# HC-05or06-Breakout.net
KiCad netlist of a schematic drawn in EAGLE
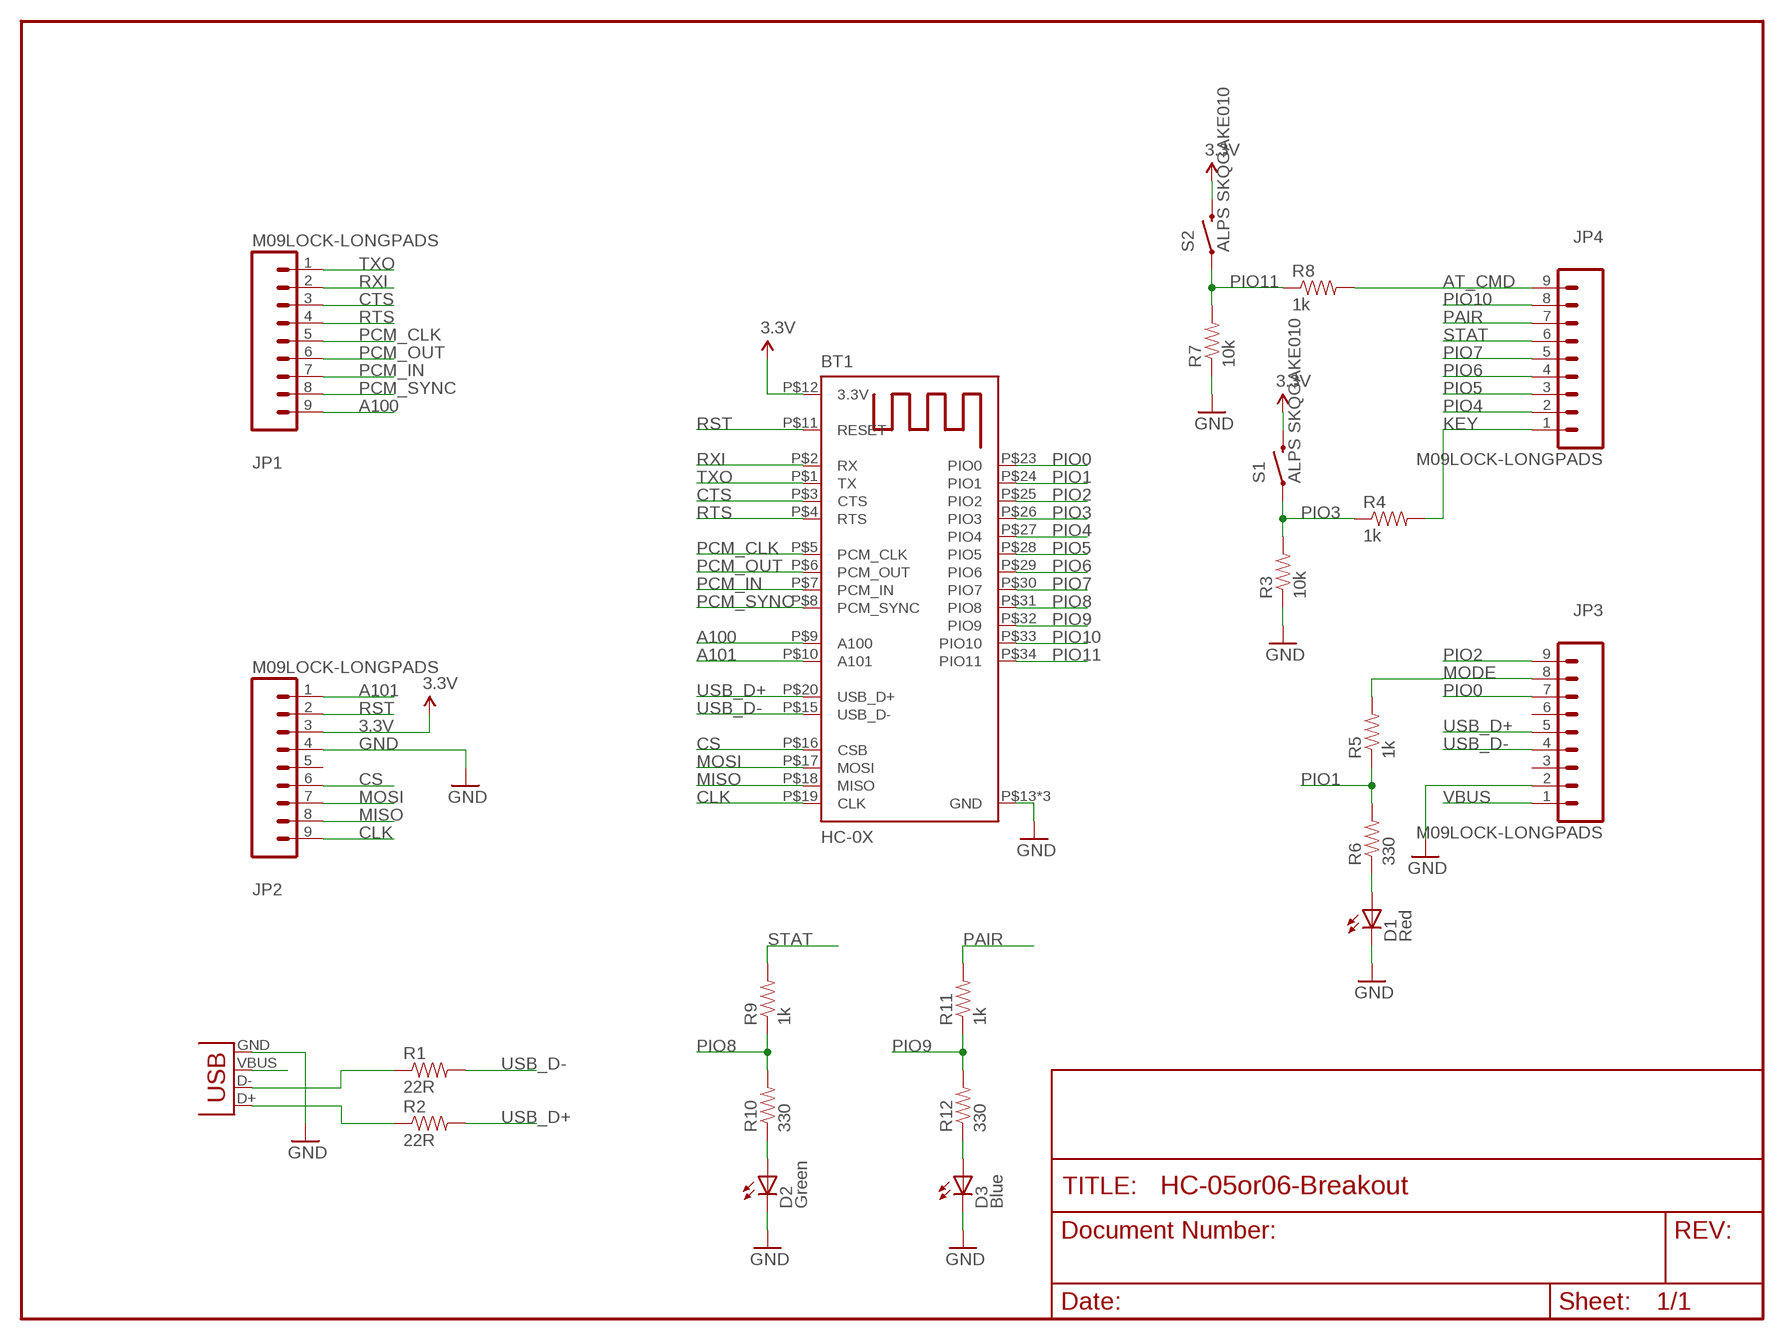
[diagram p0: schematic, sheet 1]

(export (version "E")
  (design (tool "Eeschema 10.0.6"))
  (components
    (comp (ref "BT1")
      (value "HC-0X")
      (footprint "eagle-import:HC-0X")
      (libsource (lib "eagle-import") (part "HC-0X"))
    )
    (comp (ref "D1")
      (value "Red")
      (footprint "eagle-import:LED-0603")
      (libsource (lib "eagle-import") (part "LED0603"))
    )
    (comp (ref "D2")
      (value "Green")
      (footprint "eagle-import:LED-0603")
      (libsource (lib "eagle-import") (part "LED0603"))
    )
    (comp (ref "D3")
      (value "Blue")
      (footprint "eagle-import:LED-0603")
      (libsource (lib "eagle-import") (part "LED0603"))
    )
    (comp (ref "JP1")
      (value "M09LOCK-LONGPADS")
      (footprint "eagle-import:1X09_LOCK_LONGPADS")
      (libsource (lib "eagle-import") (part "M09LOCK-LONGPADS"))
    )
    (comp (ref "JP2")
      (value "M09LOCK-LONGPADS")
      (footprint "eagle-import:1X09_LOCK_LONGPADS")
      (libsource (lib "eagle-import") (part "M09LOCK-LONGPADS"))
    )
    (comp (ref "JP3")
      (value "M09LOCK-LONGPADS")
      (footprint "eagle-import:1X09_LOCK_LONGPADS")
      (libsource (lib "eagle-import") (part "M09LOCK-LONGPADS"))
    )
    (comp (ref "JP4")
      (value "M09LOCK-LONGPADS")
      (footprint "eagle-import:1X09_LOCK_LONGPADS")
      (libsource (lib "eagle-import") (part "M09LOCK-LONGPADS"))
    )
    (comp (ref "R1")
      (value "22R")
      (footprint "eagle-import:0603-RES")
      (libsource (lib "eagle-import") (part "RESISTOR0603-RES"))
    )
    (comp (ref "R2")
      (value "22R")
      (footprint "eagle-import:0603-RES")
      (libsource (lib "eagle-import") (part "RESISTOR0603-RES"))
    )
    (comp (ref "R3")
      (value "10k")
      (footprint "eagle-import:0603-RES")
      (libsource (lib "eagle-import") (part "RESISTOR0603-RES"))
    )
    (comp (ref "R4")
      (value "1k")
      (footprint "eagle-import:0603-RES")
      (libsource (lib "eagle-import") (part "RESISTOR0603-RES"))
    )
    (comp (ref "R5")
      (value "1k")
      (footprint "eagle-import:0603-RES")
      (libsource (lib "eagle-import") (part "RESISTOR0603-RES"))
    )
    (comp (ref "R6")
      (value "330")
      (footprint "eagle-import:0603-RES")
      (libsource (lib "eagle-import") (part "RESISTOR0603-RES"))
    )
    (comp (ref "R7")
      (value "10k")
      (footprint "eagle-import:0603-RES")
      (libsource (lib "eagle-import") (part "RESISTOR0603-RES"))
    )
    (comp (ref "R8")
      (value "1k")
      (footprint "eagle-import:0603-RES")
      (libsource (lib "eagle-import") (part "RESISTOR0603-RES"))
    )
    (comp (ref "R9")
      (value "1k")
      (footprint "eagle-import:0603-RES")
      (libsource (lib "eagle-import") (part "RESISTOR0603-RES"))
    )
    (comp (ref "R10")
      (value "330")
      (footprint "eagle-import:0603-RES")
      (libsource (lib "eagle-import") (part "RESISTOR0603-RES"))
    )
    (comp (ref "R11")
      (value "1k")
      (footprint "eagle-import:0603-RES")
      (libsource (lib "eagle-import") (part "RESISTOR0603-RES"))
    )
    (comp (ref "R12")
      (value "330")
      (footprint "eagle-import:0603-RES")
      (libsource (lib "eagle-import") (part "RESISTOR0603-RES"))
    )
    (comp (ref "S1")
      (value "ALPS SKQGAKE010")
      (footprint "eagle-import:TACTILE_SWITCH_SMD")
      (libsource (lib "eagle-import") (part "SWITCH-MOMENTARY-2SMD"))
    )
    (comp (ref "S2")
      (value "ALPS SKQGAKE010")
      (footprint "eagle-import:TACTILE_SWITCH_SMD")
      (libsource (lib "eagle-import") (part "SWITCH-MOMENTARY-2SMD"))
    )
    (comp (ref "X1")
      (value "USBSMD")
      (footprint "eagle-import:USB-MINIB")
      (libsource (lib "eagle-import") (part "USBSMD"))
    )
  )
  (nets
    (net (code "1") (name "/A100") (class "Default")
      (node (ref "BT1") (pin "P$9") (pinfunction "A100_P$9") (pintype "bidirectional"))
      (node (ref "JP1") (pin "9") (pinfunction "9_9") (pintype "passive"))
    )
    (net (code "2") (name "/A101") (class "Default")
      (node (ref "BT1") (pin "P$10") (pinfunction "A101_P$10") (pintype "bidirectional"))
      (node (ref "JP2") (pin "1") (pinfunction "1_1") (pintype "passive"))
    )
    (net (code "3") (name "/AT_CMD") (class "Default")
      (node (ref "JP4") (pin "9") (pinfunction "9_9") (pintype "passive"))
      (node (ref "R8") (pin "2") (pinfunction "2_2") (pintype "passive"))
    )
    (net (code "4") (name "/CLK") (class "Default")
      (node (ref "BT1") (pin "P$19") (pinfunction "CLK_P$19") (pintype "bidirectional"))
      (node (ref "JP2") (pin "9") (pinfunction "9_9") (pintype "passive"))
    )
    (net (code "5") (name "/CS") (class "Default")
      (node (ref "BT1") (pin "P$16") (pinfunction "CSB_P$16") (pintype "bidirectional"))
      (node (ref "JP2") (pin "6") (pinfunction "6_6") (pintype "passive"))
    )
    (net (code "6") (name "/CTS") (class "Default")
      (node (ref "BT1") (pin "P$3") (pinfunction "CTS_P$3") (pintype "bidirectional"))
      (node (ref "JP1") (pin "3") (pinfunction "3_3") (pintype "passive"))
    )
    (net (code "7") (name "/KEY") (class "Default")
      (node (ref "JP4") (pin "1") (pinfunction "1_1") (pintype "passive"))
      (node (ref "R4") (pin "2") (pinfunction "2_2") (pintype "passive"))
    )
    (net (code "8") (name "/MISO") (class "Default")
      (node (ref "BT1") (pin "P$18") (pinfunction "MISO_P$18") (pintype "bidirectional"))
      (node (ref "JP2") (pin "8") (pinfunction "8_8") (pintype "passive"))
    )
    (net (code "9") (name "/MODE") (class "Default")
      (node (ref "JP3") (pin "8") (pinfunction "8_8") (pintype "passive"))
      (node (ref "R5") (pin "2") (pinfunction "2_2") (pintype "passive"))
    )
    (net (code "10") (name "/MOSI") (class "Default")
      (node (ref "BT1") (pin "P$17") (pinfunction "MOSI_P$17") (pintype "bidirectional"))
      (node (ref "JP2") (pin "7") (pinfunction "7_7") (pintype "passive"))
    )
    (net (code "11") (name "/PAIR") (class "Default")
      (node (ref "JP4") (pin "7") (pinfunction "7_7") (pintype "passive"))
      (node (ref "R11") (pin "2") (pinfunction "2_2") (pintype "passive"))
    )
    (net (code "12") (name "/PCM_CLK") (class "Default")
      (node (ref "BT1") (pin "P$5") (pinfunction "PCM_CLK_P$5") (pintype "bidirectional"))
      (node (ref "JP1") (pin "5") (pinfunction "5_5") (pintype "passive"))
    )
    (net (code "13") (name "/PCM_IN") (class "Default")
      (node (ref "BT1") (pin "P$7") (pinfunction "PCM_IN_P$7") (pintype "bidirectional"))
      (node (ref "JP1") (pin "7") (pinfunction "7_7") (pintype "passive"))
    )
    (net (code "14") (name "/PCM_OUT") (class "Default")
      (node (ref "BT1") (pin "P$6") (pinfunction "PCM_OUT_P$6") (pintype "bidirectional"))
      (node (ref "JP1") (pin "6") (pinfunction "6_6") (pintype "passive"))
    )
    (net (code "15") (name "/PCM_SYNC") (class "Default")
      (node (ref "BT1") (pin "P$8") (pinfunction "PCM_SYNC_P$8") (pintype "bidirectional"))
      (node (ref "JP1") (pin "8") (pinfunction "8_8") (pintype "passive"))
    )
    (net (code "16") (name "/PIO0") (class "Default")
      (node (ref "BT1") (pin "P$23") (pinfunction "PIO0_P$23") (pintype "bidirectional"))
      (node (ref "JP3") (pin "7") (pinfunction "7_7") (pintype "passive"))
    )
    (net (code "17") (name "/PIO1") (class "Default")
      (node (ref "BT1") (pin "P$24") (pinfunction "PIO1_P$24") (pintype "bidirectional"))
      (node (ref "R5") (pin "1") (pinfunction "1_1") (pintype "passive"))
      (node (ref "R6") (pin "2") (pinfunction "2_2") (pintype "passive"))
    )
    (net (code "18") (name "/PIO2") (class "Default")
      (node (ref "BT1") (pin "P$25") (pinfunction "PIO2_P$25") (pintype "bidirectional"))
      (node (ref "JP3") (pin "9") (pinfunction "9_9") (pintype "passive"))
    )
    (net (code "19") (name "/PIO3") (class "Default")
      (node (ref "BT1") (pin "P$26") (pinfunction "PIO3_P$26") (pintype "bidirectional"))
      (node (ref "R3") (pin "2") (pinfunction "2_2") (pintype "passive"))
      (node (ref "R4") (pin "1") (pinfunction "1_1") (pintype "passive"))
      (node (ref "S1") (pin "1") (pinfunction "1_1") (pintype "passive"))
    )
    (net (code "20") (name "/PIO4") (class "Default")
      (node (ref "BT1") (pin "P$27") (pinfunction "PIO4_P$27") (pintype "bidirectional"))
      (node (ref "JP4") (pin "2") (pinfunction "2_2") (pintype "passive"))
    )
    (net (code "21") (name "/PIO5") (class "Default")
      (node (ref "BT1") (pin "P$28") (pinfunction "PIO5_P$28") (pintype "bidirectional"))
      (node (ref "JP4") (pin "3") (pinfunction "3_3") (pintype "passive"))
    )
    (net (code "22") (name "/PIO6") (class "Default")
      (node (ref "BT1") (pin "P$29") (pinfunction "PIO6_P$29") (pintype "bidirectional"))
      (node (ref "JP4") (pin "4") (pinfunction "4_4") (pintype "passive"))
    )
    (net (code "23") (name "/PIO7") (class "Default")
      (node (ref "BT1") (pin "P$30") (pinfunction "PIO7_P$30") (pintype "bidirectional"))
      (node (ref "JP4") (pin "5") (pinfunction "5_5") (pintype "passive"))
    )
    (net (code "24") (name "/PIO8") (class "Default")
      (node (ref "BT1") (pin "P$31") (pinfunction "PIO8_P$31") (pintype "bidirectional"))
      (node (ref "R10") (pin "2") (pinfunction "2_2") (pintype "passive"))
      (node (ref "R9") (pin "1") (pinfunction "1_1") (pintype "passive"))
    )
    (net (code "25") (name "/PIO9") (class "Default")
      (node (ref "BT1") (pin "P$32") (pinfunction "PIO9_P$32") (pintype "bidirectional"))
      (node (ref "R11") (pin "1") (pinfunction "1_1") (pintype "passive"))
      (node (ref "R12") (pin "2") (pinfunction "2_2") (pintype "passive"))
    )
    (net (code "26") (name "/PIO10") (class "Default")
      (node (ref "BT1") (pin "P$33") (pinfunction "PIO10_P$33") (pintype "bidirectional"))
      (node (ref "JP4") (pin "8") (pinfunction "8_8") (pintype "passive"))
    )
    (net (code "27") (name "/PIO11") (class "Default")
      (node (ref "BT1") (pin "P$34") (pinfunction "PIO11_P$34") (pintype "bidirectional"))
      (node (ref "R7") (pin "2") (pinfunction "2_2") (pintype "passive"))
      (node (ref "R8") (pin "1") (pinfunction "1_1") (pintype "passive"))
      (node (ref "S2") (pin "1") (pinfunction "1_1") (pintype "passive"))
    )
    (net (code "28") (name "/RST") (class "Default")
      (node (ref "BT1") (pin "P$11") (pinfunction "RESET_P$11") (pintype "bidirectional"))
      (node (ref "JP2") (pin "2") (pinfunction "2_2") (pintype "passive"))
    )
    (net (code "29") (name "/RTS") (class "Default")
      (node (ref "BT1") (pin "P$4") (pinfunction "RTS_P$4") (pintype "bidirectional"))
      (node (ref "JP1") (pin "4") (pinfunction "4_4") (pintype "passive"))
    )
    (net (code "30") (name "/RXI") (class "Default")
      (node (ref "BT1") (pin "P$2") (pinfunction "RX_P$2") (pintype "bidirectional"))
      (node (ref "JP1") (pin "2") (pinfunction "2_2") (pintype "passive"))
    )
    (net (code "31") (name "/STAT") (class "Default")
      (node (ref "JP4") (pin "6") (pinfunction "6_6") (pintype "passive"))
      (node (ref "R9") (pin "2") (pinfunction "2_2") (pintype "passive"))
    )
    (net (code "32") (name "/TXO") (class "Default")
      (node (ref "BT1") (pin "P$1") (pinfunction "TX_P$1") (pintype "bidirectional"))
      (node (ref "JP1") (pin "1") (pinfunction "1_1") (pintype "passive"))
    )
    (net (code "33") (name "/USB_D+") (class "Default")
      (node (ref "BT1") (pin "P$20") (pinfunction "USB_D+_P$20") (pintype "bidirectional"))
      (node (ref "JP3") (pin "5") (pinfunction "5_5") (pintype "passive"))
      (node (ref "R2") (pin "2") (pinfunction "2_2") (pintype "passive"))
    )
    (net (code "34") (name "/USB_D-") (class "Default")
      (node (ref "BT1") (pin "P$15") (pinfunction "USB_D-_P$15") (pintype "bidirectional"))
      (node (ref "JP3") (pin "4") (pinfunction "4_4") (pintype "passive"))
      (node (ref "R1") (pin "2") (pinfunction "2_2") (pintype "passive"))
    )
    (net (code "35") (name "/VBUS") (class "Default")
      (node (ref "JP3") (pin "1") (pinfunction "1_1") (pintype "passive"))
      (node (ref "X1") (pin "VBUS") (pinfunction "VBUS_VBUS") (pintype "bidirectional"))
    )
    (net (code "36") (name "3.3V") (class "Default")
      (node (ref "BT1") (pin "P$12") (pinfunction "3.3V_P$12") (pintype "bidirectional"))
      (node (ref "JP2") (pin "3") (pinfunction "3_3") (pintype "passive"))
      (node (ref "S1") (pin "3") (pinfunction "2_3") (pintype "passive"))
      (node (ref "S2") (pin "3") (pinfunction "2_3") (pintype "passive"))
    )
    (net (code "37") (name "GND") (class "Default")
      (node (ref "BT1") (pin "P$13") (pinfunction "GND_P$13") (pintype "bidirectional"))
      (node (ref "BT1") (pin "P$21") (pinfunction "GND_P$21") (pintype "bidirectional"))
      (node (ref "BT1") (pin "P$22") (pinfunction "GND_P$22") (pintype "bidirectional"))
      (node (ref "D1") (pin "C") (pinfunction "C_C") (pintype "passive"))
      (node (ref "D2") (pin "C") (pinfunction "C_C") (pintype "passive"))
      (node (ref "D3") (pin "C") (pinfunction "C_C") (pintype "passive"))
      (node (ref "JP2") (pin "4") (pinfunction "4_4") (pintype "passive"))
      (node (ref "JP3") (pin "2") (pinfunction "2_2") (pintype "passive"))
      (node (ref "R3") (pin "1") (pinfunction "1_1") (pintype "passive"))
      (node (ref "R7") (pin "1") (pinfunction "1_1") (pintype "passive"))
      (node (ref "X1") (pin "GND") (pinfunction "GND_GND") (pintype "bidirectional"))
    )
    (net (code "38") (name "Net-(D1-PadA)") (class "Default")
      (node (ref "D1") (pin "A") (pinfunction "A_A") (pintype "passive"))
      (node (ref "R6") (pin "1") (pinfunction "1_1") (pintype "passive"))
    )
    (net (code "39") (name "Net-(D2-PadA)") (class "Default")
      (node (ref "D2") (pin "A") (pinfunction "A_A") (pintype "passive"))
      (node (ref "R10") (pin "1") (pinfunction "1_1") (pintype "passive"))
    )
    (net (code "40") (name "Net-(D3-PadA)") (class "Default")
      (node (ref "D3") (pin "A") (pinfunction "A_A") (pintype "passive"))
      (node (ref "R12") (pin "1") (pinfunction "1_1") (pintype "passive"))
    )
    (net (code "41") (name "Net-(R1-Pad1)") (class "Default")
      (node (ref "R1") (pin "1") (pinfunction "1_1") (pintype "passive"))
      (node (ref "X1") (pin "D-") (pinfunction "D-_D-") (pintype "bidirectional"))
    )
    (net (code "42") (name "Net-(R2-Pad1)") (class "Default")
      (node (ref "R2") (pin "1") (pinfunction "1_1") (pintype "passive"))
      (node (ref "X1") (pin "D+") (pinfunction "D+_D+") (pintype "bidirectional"))
    )
    (net (code "43") (name "unconnected-(JP2-Pad5)") (class "Default")
      (node (ref "JP2") (pin "5") (pinfunction "5_5") (pintype "passive"))
    )
    (net (code "44") (name "unconnected-(JP3-Pad3)") (class "Default")
      (node (ref "JP3") (pin "3") (pinfunction "3_3") (pintype "passive"))
    )
    (net (code "45") (name "unconnected-(JP3-Pad6)") (class "Default")
      (node (ref "JP3") (pin "6") (pinfunction "6_6") (pintype "passive"))
    )
  )
)
